# Sheet1.net
KiCad netlist of a schematic drawn in Altium Designer
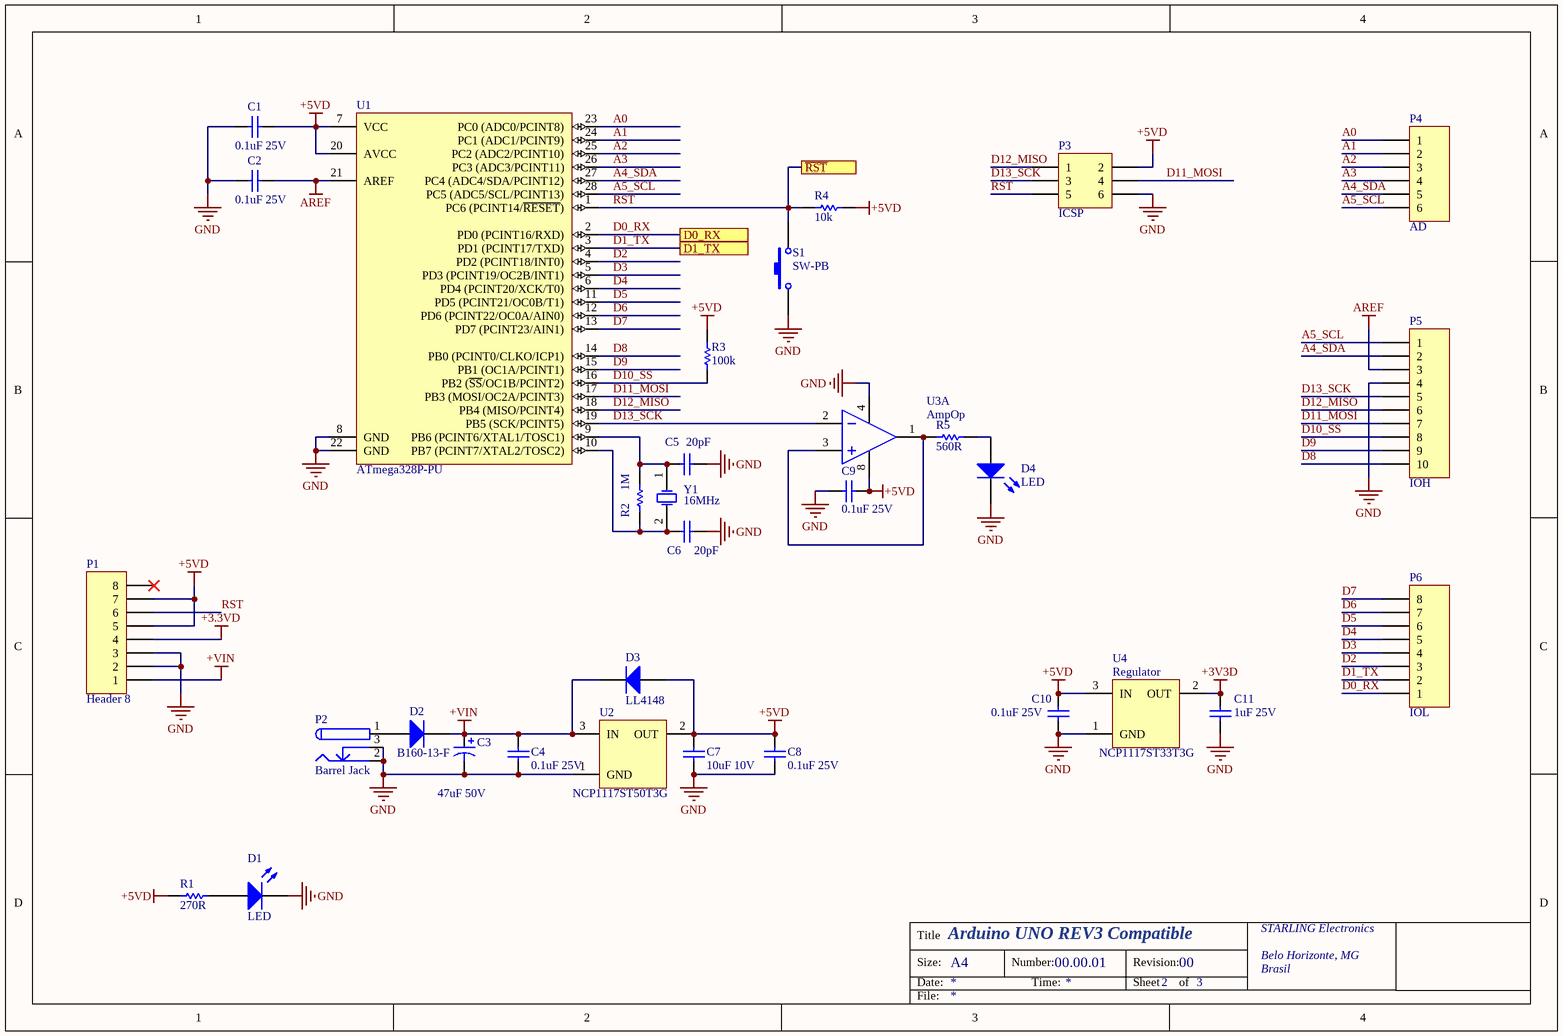
[diagram p0: Sheet1.SchDoc]

(export (version "E")
  (design (tool "Eeschema 10.0.6"))
  (components
    (comp (ref "C1")
      (value "0.1uF 25V")
      (footprint "C1608[0603]")
      (description "Capacitor")
      (fields (field (name "MANUFACTURER PART NUMBER") "GCM188R71E104KA57D") (field (name "TOLERANCE") "10%"))
      (libsource (lib "Basic Library") (part "C"))
    )
    (comp (ref "C2")
      (value "0.1uF 25V")
      (footprint "C1608[0603]")
      (description "Capacitor")
      (fields (field (name "MANUFACTURER PART NUMBER") "GCM188R71E104KA57D") (field (name "TOLERANCE") "10%"))
      (libsource (lib "Basic Library") (part "C"))
    )
    (comp (ref "C3")
      (value "47uF 50V")
      (footprint "Cap_Al_SMD_C6_6.6x6.6mm")
      (description "Polarized Capacitor")
      (fields (field (name "MANUFACTURER PART NUMBER") "EEE-1EA470WP") (field (name "TOLERANCE") "20%"))
      (libsource (lib "Basic Library") (part "CP"))
    )
    (comp (ref "C4")
      (value "0.1uF 25V")
      (footprint "C1608[0603]")
      (description "Capacitor")
      (fields (field (name "MANUFACTURER PART NUMBER") "C0603C104Z3VACTU") (field (name "TOLERANCE") "80%"))
      (libsource (lib "Basic Library") (part "C"))
    )
    (comp (ref "C5")
      (value "20pF")
      (footprint "C1608[0603]")
      (description "Capacitor")
      (fields (field (name "MANUFACTURER PART NUMBER") "CL10C200JB8NNNC") (field (name "TOLERANCE") "5%"))
      (libsource (lib "Basic Library") (part "C"))
    )
    (comp (ref "C6")
      (value "20pF")
      (footprint "C1608[0603]")
      (description "Capacitor")
      (fields (field (name "MANUFACTURER PART NUMBER") "CL10C200JB8NNNC") (field (name "TOLERANCE") "5%"))
      (libsource (lib "Basic Library") (part "C"))
    )
    (comp (ref "C7")
      (value "10uF 10V")
      (footprint "C2012[0805]")
      (description "Capacitor")
      (fields
        (field (name "MANUFACTURER PART NUMBER") "C2012X7R1A106K125AC")
        (field (name "TOLERANCE") "10%")
      )
      (libsource (lib "Basic Library") (part "C"))
    )
    (comp (ref "C8")
      (value "0.1uF 25V")
      (footprint "C1608[0603]")
      (description "Capacitor")
      (libsource (lib "Basic Library") (part "C"))
    )
    (comp (ref "C9")
      (value "0.1uF 25V")
      (footprint "C1608[0603]")
      (description "Capacitor")
      (fields (field (name "MANUFACTURER PART NUMBER") "GCM188R71E104KA57D") (field (name "TOLERANCE") "10%"))
      (libsource (lib "Basic Library") (part "C"))
    )
    (comp (ref "C10")
      (value "0.1uF 25V")
      (footprint "C1608[0603]")
      (description "Capacitor")
      (fields (field (name "MANUFACTURER PART NUMBER") "GCM188R71E104KA57D") (field (name "TOLERANCE") "10%"))
      (libsource (lib "Basic Library") (part "C"))
    )
    (comp (ref "C11")
      (value "1uF 25V")
      (footprint "C2012[0805]")
      (description "Capacitor")
      (fields
        (field (name "MANUFACTURER") "TDK")
        (field (name "MANUFACTURER PART NUMBER") "C2012X7R1E105K125AB")
      )
      (libsource (lib "Basic Library") (part "C"))
    )
    (comp (ref "D1")
      (value "LED")
      (footprint "LED-0603-G")
      (fields (field (name "MANUFACTURER PART NUMBER") "598-8070-102F"))
      (libsource (lib "Basic Library") (part "LED"))
    )
    (comp (ref "D2")
      (value "B160-13-F")
      (footprint "DO214AC")
      (description "Diode")
      (libsource (lib "Basic Library") (part "D"))
    )
    (comp (ref "D3")
      (value "LL4148")
      (footprint "SOD-80/MLL34")
      (description "Diode")
      (fields (field (name "VOLTAGE") "100V"))
      (libsource (lib "Basic Library") (part "D"))
    )
    (comp (ref "D4")
      (value "LED")
      (footprint "LED-0603-R")
      (fields (field (name "MANUFACTURER PART NUMBER") "LTST-C191KRKT") (field (name "VOLTAGE") "2V"))
      (libsource (lib "Basic Library") (part "LED"))
    )
    (comp (ref "P1")
      (value "Header 8")
      (footprint "HDR1X8F")
      (description "Header, 8-Pin")
      (fields (field (name "PUBLISHER") "Altium Limited"))
      (libsource (lib "Connectors Library") (part "Header 8"))
    )
    (comp (ref "P2")
      (value "Barrel Jack")
      (footprint "BARREL2.5")
      (description "Low Voltage Power Supply Connector")
      (fields
        (field (name "MANUFACTURER") "Memory Protection Devices")
        (field (name "MANUFACTURER PART NUMBER") "EJ503A")
      )
      (libsource (lib "Connectors Library") (part "PWR2.5"))
    )
    (comp (ref "P3")
      (value "ICSP")
      (footprint "HDR2X3M")
      (description "Header, 3-Pin, Dual row")
      (fields
        (field (name "MANUFACTURER") "Harwin")
        (field (name "MANUFACTURER PART NUMBER") "M20-9720345")
        (field (name "PUBLISHER") "Altium Limited")
      )
      (libsource (lib "Connectors Library") (part "Header 3X2"))
    )
    (comp (ref "P4")
      (value "AD")
      (footprint "HDR1X6m")
      (description "Header, 6-Pin")
      (fields (field (name "PUBLISHER") "Altium Limited"))
      (libsource (lib "Connectors Library") (part "Header 6"))
    )
    (comp (ref "P5")
      (value "IOH")
      (footprint "HDR1X10")
      (libsource (lib "Connectors Library") (part "Header 10"))
    )
    (comp (ref "P6")
      (value "IOL")
      (footprint "HDR1X8F")
      (description "Header, 8-Pin")
      (fields
        (field (name "MANUFACTURER") "Sullins")
        (field (name "MANUFACTURER PART NUMBER") "PPTC081LFBN-RC")
        (field (name "PUBLISHER") "Altium Limited")
      )
      (libsource (lib "") (part "Header 8_1"))
    )
    (comp (ref "R1")
      (value "270R")
      (footprint "R1608[0603]")
      (description "Resistor")
      (fields (field (name "MANUFACTURER PART NUMBER") "CRCW0603-0000Z0EA") (field (name "TOLERANCE") "5%"))
      (libsource (lib "Basic Library") (part "R"))
    )
    (comp (ref "R2")
      (value "1M")
      (footprint "R2012[0805]")
      (description "Resistor")
      (fields (field (name "MANUFACTURER PART NUMBER") "ERA-6AEB105V") (field (name "TOLERANCE") "1%"))
      (libsource (lib "Basic Library") (part "R"))
    )
    (comp (ref "R3")
      (value "100k")
      (footprint "R1608[0603]")
      (description "Resistor")
      (fields (field (name "MANUFACTURER PART NUMBER") "MCT06030C1003FP500") (field (name "TOLERANCE") "1%"))
      (libsource (lib "Basic Library") (part "R"))
    )
    (comp (ref "R4")
      (value "10k")
      (footprint "R1608[0603]")
      (description "Resistor")
      (fields (field (name "MANUFACTURER PART NUMBER") "MCT06030C1002FP500") (field (name "TOLERANCE") "1%"))
      (libsource (lib "Basic Library") (part "R"))
    )
    (comp (ref "R5")
      (value "560R")
      (footprint "R1608[0603]")
      (description "Resistor")
      (fields (field (name "MANUFACTURER PART NUMBER") "AC0603FR-07560RL") (field (name "TOLERANCE") "1%"))
      (libsource (lib "Basic Library") (part "R"))
    )
    (comp (ref "S1")
      (value "SW-PB")
      (footprint "PB-SW-SMT")
      (description "Tactile Switch")
      (fields (field (name "MANUFACTURER PART NUMBER") "PTS645SM43SMTR92LFS"))
      (libsource (lib "Basic Library") (part "SW Tact"))
    )
    (comp (ref "U1")
      (value "ATmega328P-PU")
      (footprint "DIP28")
      (libsource (lib "Components Library") (part "ATmega328P-PU"))
    )
    (comp (ref "U2")
      (value "NCP1117ST50T3G")
      (footprint "SOT223_N")
      (fields (field (name "TOLERANCE") "1%"))
      (libsource (lib "Basic Library") (part "Regulator"))
    )
    (comp (ref "U3")
      (value "AmpOp")
      (footprint "TSSOP-8")
      (fields
        (field (name "MANUFACTURER") "Texas Instruments")
        (field (name "MANUFACTURER PART NUMBER") "LM358PWR")
      )
      (libsource (lib "Components Library") (part "LM358PWR"))
    )
    (comp (ref "U4")
      (value "Regulator")
      (footprint "SOT223_N")
      (fields
        (field (name "MANUFACTURER") "ON Semiconductor")
        (field (name "MANUFACTURER PART NUMBER") "NCP1117ST33T3G")
      )
      (libsource (lib "Symbols") (part "Regulator"))
    )
    (comp (ref "Y1")
      (value "16MHz")
      (footprint "CRYSTAL-HC49/4H_SMX")
      (description "Crystal Oscillator")
      (fields (field (name "MANUFACTURER PART NUMBER") "ECS-160-20-3X-TR") (field (name "TOLERANCE") "30ppm"))
      (libsource (lib "Basic Library") (part "XTAL"))
    )
  )
  (nets
    (net (code "1") (name "+3.3VD") (class "Default")
      (node (ref "P1") (pin "4") (pinfunction "4_4") (pintype "passive"))
    )
    (net (code "2") (name "+3V3D") (class "Default")
      (node (ref "C11") (pin "2") (pinfunction "2_2") (pintype "passive"))
      (node (ref "U4") (pin "2") (pinfunction "OUT_2") (pintype "passive"))
    )
    (net (code "3") (name "+5VD") (class "Default")
      (node (ref "C1") (pin "1") (pinfunction "1_1") (pintype "passive"))
      (node (ref "C10") (pin "2") (pinfunction "2_2") (pintype "passive"))
      (node (ref "C7") (pin "2") (pinfunction "2_2") (pintype "passive"))
      (node (ref "C8") (pin "2") (pinfunction "2_2") (pintype "passive"))
      (node (ref "C9") (pin "1") (pinfunction "1_1") (pintype "passive"))
      (node (ref "D3") (pin "1") (pinfunction "A_1") (pintype "passive"))
      (node (ref "P1") (pin "5") (pinfunction "5_5") (pintype "passive"))
      (node (ref "P1") (pin "7") (pinfunction "7_7") (pintype "passive"))
      (node (ref "P3") (pin "2") (pinfunction "2_2") (pintype "passive"))
      (node (ref "R1") (pin "1") (pinfunction "1_1") (pintype "passive"))
      (node (ref "R3") (pin "1") (pinfunction "1_1") (pintype "passive"))
      (node (ref "R4") (pin "1") (pinfunction "1_1") (pintype "passive"))
      (node (ref "U1") (pin "20") (pinfunction "AVCC_20") (pintype "power_in"))
      (node (ref "U1") (pin "7") (pinfunction "VCC_7") (pintype "power_in"))
      (node (ref "U2") (pin "2") (pinfunction "OUT_2") (pintype "passive"))
      (node (ref "U3") (pin "8") (pinfunction "V-_8") (pintype "passive"))
      (node (ref "U4") (pin "3") (pinfunction "IN_3") (pintype "passive"))
    )
    (net (code "4") (name "+VIN") (class "Default")
      (node (ref "C3") (pin "1") (pinfunction "1_1") (pintype "passive"))
      (node (ref "C4") (pin "2") (pinfunction "2_2") (pintype "passive"))
      (node (ref "D2") (pin "2") (pinfunction "K_2") (pintype "passive"))
      (node (ref "D3") (pin "2") (pinfunction "K_2") (pintype "passive"))
      (node (ref "P1") (pin "1") (pinfunction "1_1") (pintype "passive"))
      (node (ref "U2") (pin "3") (pinfunction "IN_3") (pintype "passive"))
    )
    (net (code "5") (name "/A0") (class "Default")
      (node (ref "P4") (pin "1") (pinfunction "1_1") (pintype "passive"))
      (node (ref "U1") (pin "23") (pinfunction "PC0_(ADC0/PCINT8)_23") (pintype "bidirectional"))
    )
    (net (code "6") (name "/A1") (class "Default")
      (node (ref "P4") (pin "2") (pinfunction "2_2") (pintype "passive"))
      (node (ref "U1") (pin "24") (pinfunction "PC1_(ADC1/PCINT9)_24") (pintype "bidirectional"))
    )
    (net (code "7") (name "/A2") (class "Default")
      (node (ref "P4") (pin "3") (pinfunction "3_3") (pintype "passive"))
      (node (ref "U1") (pin "25") (pinfunction "PC2_(ADC2/PCINT10)_25") (pintype "bidirectional"))
    )
    (net (code "8") (name "/A3") (class "Default")
      (node (ref "P4") (pin "4") (pinfunction "4_4") (pintype "passive"))
      (node (ref "U1") (pin "26") (pinfunction "PC3_(ADC3/PCINT11)_26") (pintype "bidirectional"))
    )
    (net (code "9") (name "/A4_SDA") (class "Default")
      (node (ref "P4") (pin "5") (pinfunction "5_5") (pintype "passive"))
      (node (ref "P5") (pin "2") (pinfunction "2_2") (pintype "passive"))
      (node (ref "U1") (pin "27") (pinfunction "PC4_(ADC4/SDA/PCINT12)_27") (pintype "bidirectional"))
    )
    (net (code "10") (name "/A5_SCL") (class "Default")
      (node (ref "P4") (pin "6") (pinfunction "6_6") (pintype "passive"))
      (node (ref "P5") (pin "1") (pinfunction "1_1") (pintype "passive"))
      (node (ref "U1") (pin "28") (pinfunction "PC5_(ADC5/SCL/PCINT13)_28") (pintype "bidirectional"))
    )
    (net (code "11") (name "/D0_RX") (class "Default")
      (node (ref "P6") (pin "1") (pinfunction "1_1") (pintype "passive"))
      (node (ref "U1") (pin "2") (pinfunction "PD0_(PCINT16/RXD)_2") (pintype "bidirectional"))
    )
    (net (code "12") (name "/D1_TX") (class "Default")
      (node (ref "P6") (pin "2") (pinfunction "2_2") (pintype "passive"))
      (node (ref "U1") (pin "3") (pinfunction "PD1_(PCINT17/TXD)_3") (pintype "bidirectional"))
    )
    (net (code "13") (name "/D2") (class "Default")
      (node (ref "P6") (pin "3") (pinfunction "3_3") (pintype "passive"))
      (node (ref "U1") (pin "4") (pinfunction "PD2_(PCINT18/INT0)_4") (pintype "bidirectional"))
    )
    (net (code "14") (name "/D3") (class "Default")
      (node (ref "P6") (pin "4") (pinfunction "4_4") (pintype "passive"))
      (node (ref "U1") (pin "5") (pinfunction "PD3_(PCINT19/OC2B/INT1)_5") (pintype "bidirectional"))
    )
    (net (code "15") (name "/D4") (class "Default")
      (node (ref "P6") (pin "5") (pinfunction "5_5") (pintype "passive"))
      (node (ref "U1") (pin "6") (pinfunction "PD4_(PCINT20/XCK/T0)_6") (pintype "bidirectional"))
    )
    (net (code "16") (name "/D5") (class "Default")
      (node (ref "P6") (pin "6") (pinfunction "6_6") (pintype "passive"))
      (node (ref "U1") (pin "11") (pinfunction "PD5_(PCINT21/OC0B/T1)_11") (pintype "bidirectional"))
    )
    (net (code "17") (name "/D6") (class "Default")
      (node (ref "P6") (pin "7") (pinfunction "7_7") (pintype "passive"))
      (node (ref "U1") (pin "12") (pinfunction "PD6_(PCINT22/OC0A/AIN0)_12") (pintype "bidirectional"))
    )
    (net (code "18") (name "/D7") (class "Default")
      (node (ref "P6") (pin "8") (pinfunction "8_8") (pintype "passive"))
      (node (ref "U1") (pin "13") (pinfunction "PD7_(PCINT23/AIN1)_13") (pintype "bidirectional"))
    )
    (net (code "19") (name "/D8") (class "Default")
      (node (ref "P5") (pin "10") (pinfunction "10_10") (pintype "passive"))
      (node (ref "U1") (pin "14") (pinfunction "PB0_(PCINT0/CLKO/ICP1)_14") (pintype "bidirectional"))
    )
    (net (code "20") (name "/D9") (class "Default")
      (node (ref "P5") (pin "9") (pinfunction "9_9") (pintype "passive"))
      (node (ref "U1") (pin "15") (pinfunction "PB1_(OC1A/PCINT1)_15") (pintype "bidirectional"))
    )
    (net (code "21") (name "/D10_SS") (class "Default")
      (node (ref "P5") (pin "8") (pinfunction "8_8") (pintype "passive"))
      (node (ref "R3") (pin "2") (pinfunction "2_2") (pintype "passive"))
      (node (ref "U1") (pin "16") (pinfunction "PB2_(~{SS}/OC1B/PCINT2)_16") (pintype "bidirectional"))
    )
    (net (code "22") (name "/D11_MOSI") (class "Default")
      (node (ref "P3") (pin "4") (pinfunction "4_4") (pintype "passive"))
      (node (ref "P5") (pin "7") (pinfunction "7_7") (pintype "passive"))
      (node (ref "U1") (pin "17") (pinfunction "PB3_(MOSI/OC2A/PCINT3)_17") (pintype "bidirectional"))
    )
    (net (code "23") (name "/D12_MISO") (class "Default")
      (node (ref "P3") (pin "1") (pinfunction "1_1") (pintype "passive"))
      (node (ref "P5") (pin "6") (pinfunction "6_6") (pintype "passive"))
      (node (ref "U1") (pin "18") (pinfunction "PB4_(MISO/PCINT4)_18") (pintype "bidirectional"))
    )
    (net (code "24") (name "/D13_SCK") (class "Default")
      (node (ref "P3") (pin "3") (pinfunction "3_3") (pintype "passive"))
      (node (ref "P5") (pin "5") (pinfunction "5_5") (pintype "passive"))
      (node (ref "U1") (pin "19") (pinfunction "PB5_(SCK/PCINT5)_19") (pintype "bidirectional"))
      (node (ref "U3") (pin "2") (pinfunction "IN-_2") (pintype "passive"))
    )
    (net (code "25") (name "/RST") (class "Default")
      (node (ref "P1") (pin "6") (pinfunction "6_6") (pintype "passive"))
    )
    (net (code "26") (name "/~{RST}") (class "Default")
      (node (ref "P3") (pin "5") (pinfunction "5_5") (pintype "passive"))
      (node (ref "R4") (pin "2") (pinfunction "2_2") (pintype "passive"))
      (node (ref "S1") (pin "2") (pinfunction "2_2") (pintype "passive"))
      (node (ref "U1") (pin "1") (pinfunction "PC6_(PCINT14/~{RESET})_1") (pintype "bidirectional"))
    )
    (net (code "27") (name "AREF") (class "Default")
      (node (ref "C2") (pin "1") (pinfunction "1_1") (pintype "passive"))
      (node (ref "P5") (pin "3") (pinfunction "3_3") (pintype "passive"))
      (node (ref "U1") (pin "21") (pinfunction "AREF_21") (pintype "power_in"))
    )
    (net (code "28") (name "GND") (class "Default")
      (node (ref "C1") (pin "2") (pinfunction "2_2") (pintype "passive"))
      (node (ref "C10") (pin "1") (pinfunction "1_1") (pintype "passive"))
      (node (ref "C11") (pin "1") (pinfunction "1_1") (pintype "passive"))
      (node (ref "C2") (pin "2") (pinfunction "2_2") (pintype "passive"))
      (node (ref "C3") (pin "2") (pinfunction "2_2") (pintype "passive"))
      (node (ref "C4") (pin "1") (pinfunction "1_1") (pintype "passive"))
      (node (ref "C5") (pin "2") (pinfunction "2_2") (pintype "passive"))
      (node (ref "C6") (pin "2") (pinfunction "2_2") (pintype "passive"))
      (node (ref "C7") (pin "1") (pinfunction "1_1") (pintype "passive"))
      (node (ref "C8") (pin "1") (pinfunction "1_1") (pintype "passive"))
      (node (ref "C9") (pin "2") (pinfunction "2_2") (pintype "passive"))
      (node (ref "D1") (pin "2") (pinfunction "K_2") (pintype "passive"))
      (node (ref "D4") (pin "2") (pinfunction "K_2") (pintype "passive"))
      (node (ref "P1") (pin "2") (pinfunction "2_2") (pintype "passive"))
      (node (ref "P1") (pin "3") (pinfunction "3_3") (pintype "passive"))
      (node (ref "P2") (pin "2") (pinfunction "2_2") (pintype "passive"))
      (node (ref "P2") (pin "3") (pinfunction "3_3") (pintype "passive"))
      (node (ref "P3") (pin "6") (pinfunction "6_6") (pintype "passive"))
      (node (ref "P5") (pin "4") (pinfunction "4_4") (pintype "passive"))
      (node (ref "S1") (pin "1") (pinfunction "1_1") (pintype "passive"))
      (node (ref "U1") (pin "22") (pinfunction "GND_22") (pintype "power_in"))
      (node (ref "U1") (pin "8") (pinfunction "GND_8") (pintype "power_in"))
      (node (ref "U2") (pin "1") (pinfunction "GND_1") (pintype "passive"))
      (node (ref "U3") (pin "4") (pinfunction "V+_4") (pintype "passive"))
      (node (ref "U4") (pin "1") (pinfunction "GND_1") (pintype "passive"))
    )
    (net (code "29") (name "Net-(D1-A)") (class "Default")
      (node (ref "D1") (pin "1") (pinfunction "A_1") (pintype "passive"))
      (node (ref "R1") (pin "2") (pinfunction "2_2") (pintype "passive"))
    )
    (net (code "30") (name "Net-(D2-A)") (class "Default")
      (node (ref "D2") (pin "1") (pinfunction "A_1") (pintype "passive"))
      (node (ref "P2") (pin "1") (pinfunction "1_1") (pintype "passive"))
    )
    (net (code "31") (name "Net-(D4-A)") (class "Default")
      (node (ref "D4") (pin "1") (pinfunction "A_1") (pintype "passive"))
      (node (ref "R5") (pin "2") (pinfunction "2_2") (pintype "passive"))
    )
    (net (code "32") (name "Net-(U1-PB6_(PCINT6{slash}XTAL1{slash}TOSC1))") (class "Default")
      (node (ref "C5") (pin "1") (pinfunction "1_1") (pintype "passive"))
      (node (ref "R2") (pin "2") (pinfunction "2_2") (pintype "passive"))
      (node (ref "U1") (pin "9") (pinfunction "PB6_(PCINT6/XTAL1/TOSC1)_9") (pintype "bidirectional"))
      (node (ref "Y1") (pin "1") (pinfunction "OSC1_1") (pintype "passive"))
    )
    (net (code "33") (name "Net-(U1-PB7_(PCINT7{slash}XTAL2{slash}TOSC2))") (class "Default")
      (node (ref "C6") (pin "1") (pinfunction "1_1") (pintype "passive"))
      (node (ref "R2") (pin "1") (pinfunction "1_1") (pintype "passive"))
      (node (ref "U1") (pin "10") (pinfunction "PB7_(PCINT7/XTAL2/TOSC2)_10") (pintype "bidirectional"))
      (node (ref "Y1") (pin "2") (pinfunction "OSC2_2") (pintype "passive"))
    )
    (net (code "34") (name "Net-(U3A-IN+)") (class "Default")
      (node (ref "R5") (pin "1") (pinfunction "1_1") (pintype "passive"))
      (node (ref "U3") (pin "1") (pinfunction "OUT_1") (pintype "passive"))
      (node (ref "U3") (pin "3") (pinfunction "IN+_3") (pintype "passive"))
    )
    (net (code "35") (name "unconnected-(P1-Pad8)") (class "Default")
      (node (ref "P1") (pin "8") (pinfunction "8_8") (pintype "passive+no_connect"))
    )
  )
)
